# ESP32_radio_rev1_0.net
KiCad netlist of a schematic drawn in EAGLE
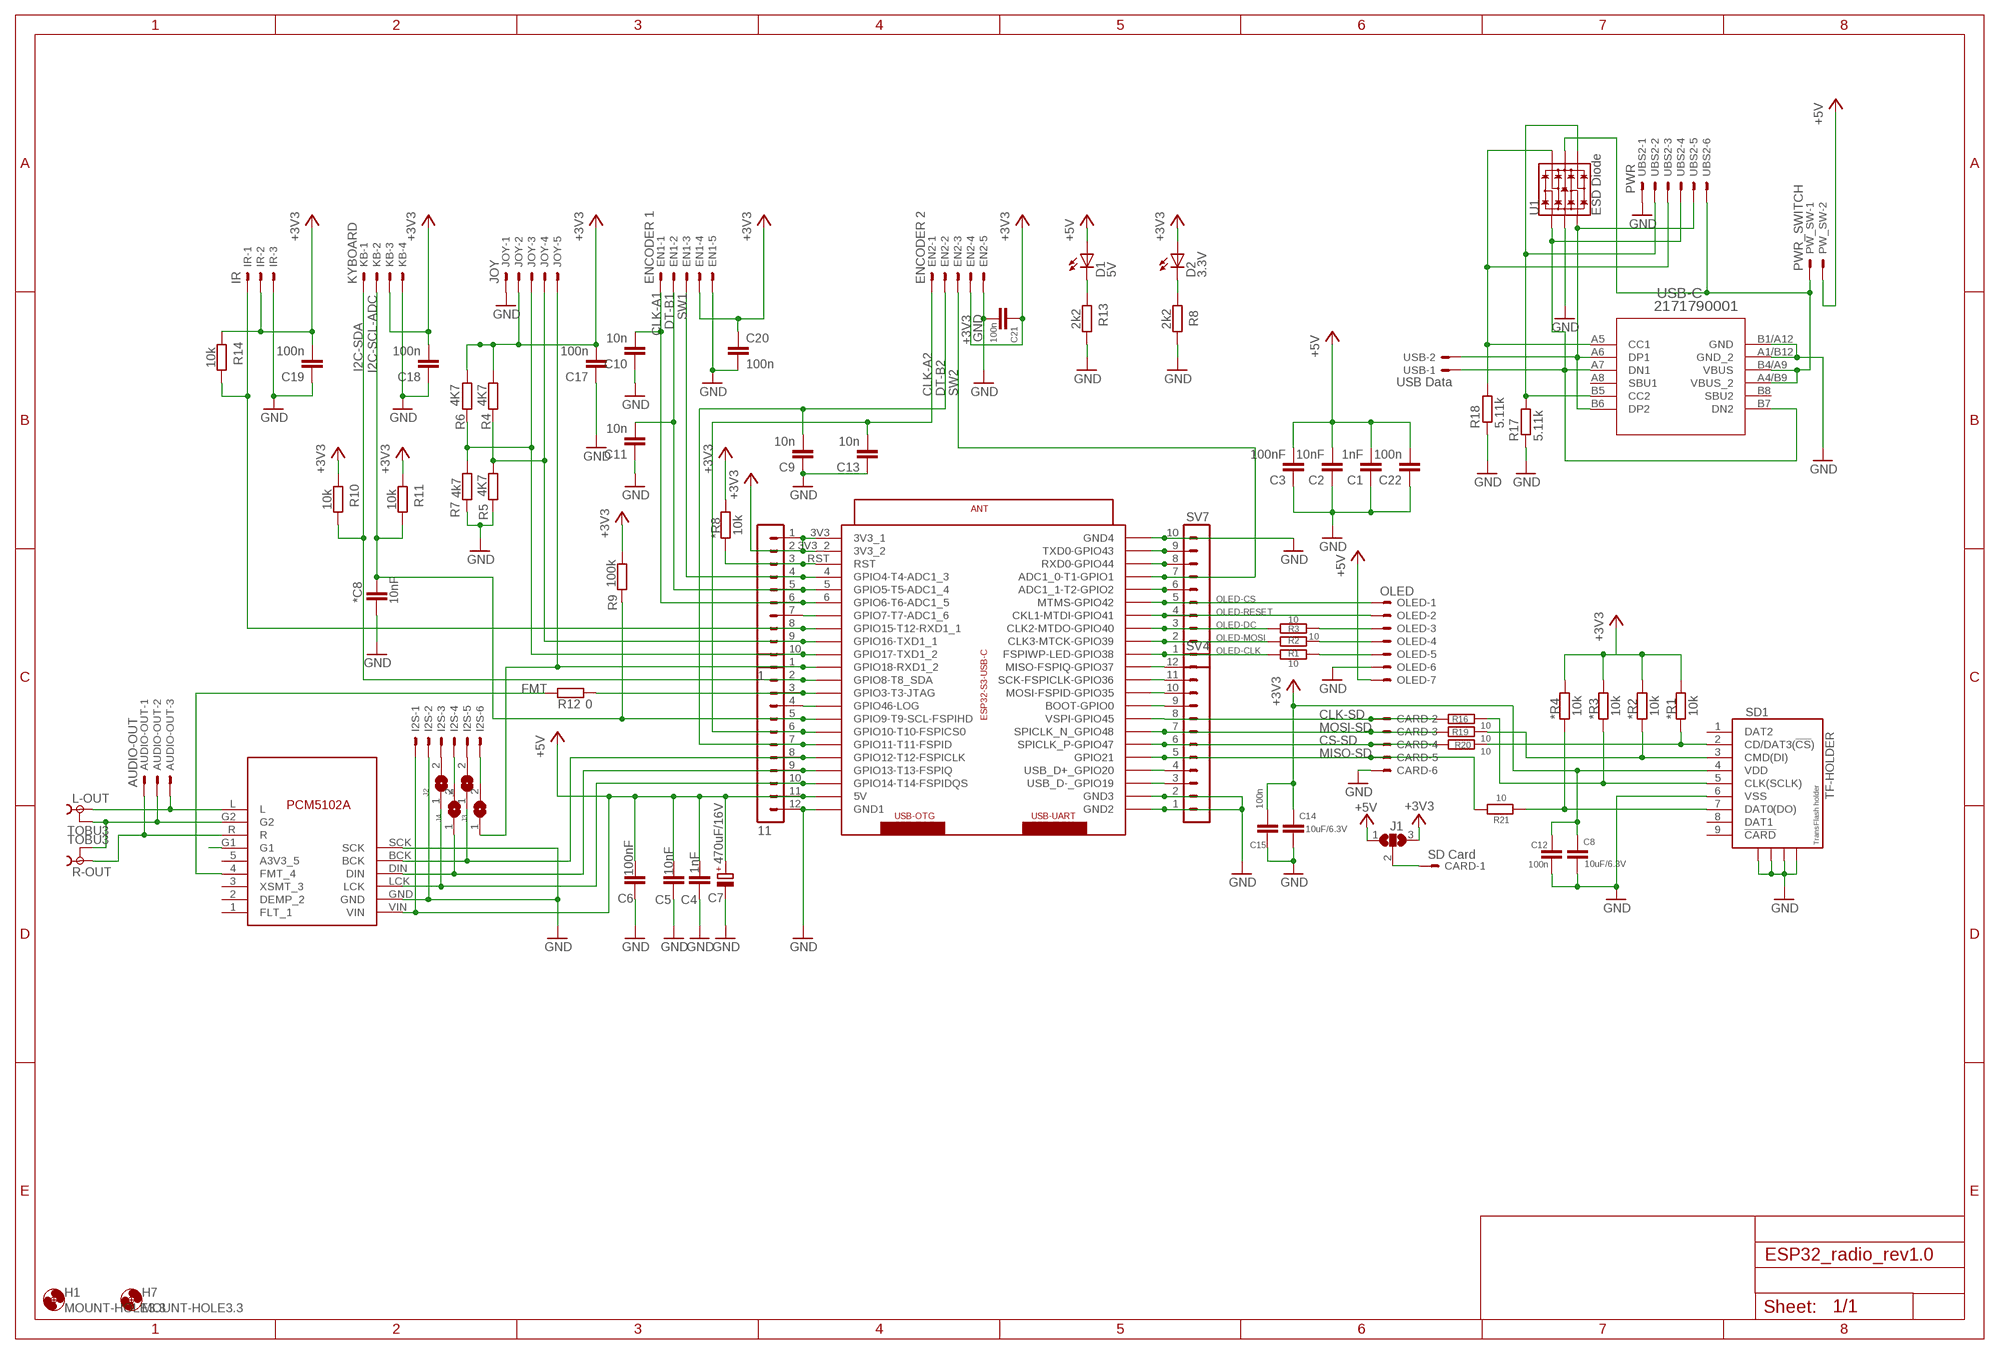
[diagram p0: schematic, sheet 1]

(export (version "E")
  (design (tool "Eeschema 10.0.6"))
  (components
    (comp (ref "*C8")
      (value "10nF")
      (footprint "eagle-import:C0603")
      (libsource (lib "eagle-import") (part "C-EUC0603"))
    )
    (comp (ref "*R1")
      (value "10k")
      (footprint "eagle-import:R0603")
      (libsource (lib "eagle-import") (part "R-EU_R0603"))
    )
    (comp (ref "*R2")
      (value "10k")
      (footprint "eagle-import:R0603")
      (libsource (lib "eagle-import") (part "R-EU_R0603"))
    )
    (comp (ref "*R3")
      (value "10k")
      (footprint "eagle-import:R0603")
      (libsource (lib "eagle-import") (part "R-EU_R0603"))
    )
    (comp (ref "*R4")
      (value "10k")
      (footprint "eagle-import:R0603")
      (libsource (lib "eagle-import") (part "R-EU_R0603"))
    )
    (comp (ref "*R8")
      (value "10k")
      (footprint "eagle-import:R0603")
      (libsource (lib "eagle-import") (part "R-EU_R0603"))
    )
    (comp (ref "1")
      (value "MA10-1")
      (footprint "eagle-import:MA10-1")
      (libsource (lib "eagle-import") (part "MA10-1"))
    )
    (comp (ref "11")
      (value "MA12-1")
      (footprint "eagle-import:MA12-1")
      (libsource (lib "eagle-import") (part "MA12-1"))
    )
    (comp (ref "AUDIO-OUT")
      (value "AUDIO-OUT")
      (footprint "eagle-import:JST-XH-03-PACKAGE-LONG-PAD")
      (libsource (lib "eagle-import") (part "JST-XH-03-PIN-LONG-PAD"))
    )
    (comp (ref "C1")
      (value "1nF")
      (footprint "eagle-import:C0603")
      (libsource (lib "eagle-import") (part "C-EUC0603"))
    )
    (comp (ref "C2")
      (value "10nF")
      (footprint "eagle-import:C0603")
      (libsource (lib "eagle-import") (part "C-EUC0603"))
    )
    (comp (ref "C3")
      (value "100nF")
      (footprint "eagle-import:C0603")
      (libsource (lib "eagle-import") (part "C-EUC0603"))
    )
    (comp (ref "C4")
      (value "1nF")
      (footprint "eagle-import:C0603")
      (libsource (lib "eagle-import") (part "C-EUC0603"))
    )
    (comp (ref "C5")
      (value "10nF")
      (footprint "eagle-import:C0603")
      (libsource (lib "eagle-import") (part "C-EUC0603"))
    )
    (comp (ref "C6")
      (value "100nF")
      (footprint "eagle-import:C0603")
      (libsource (lib "eagle-import") (part "C-EUC0603"))
    )
    (comp (ref "C7")
      (value "470uF/16V")
      (footprint "eagle-import:150CLZ-1010")
      (libsource (lib "eagle-import") (part "CPOL-EU150CLZ-1010"))
    )
    (comp (ref "C8")
      (value "10uF/6.3V")
      (footprint "eagle-import:C1210")
      (libsource (lib "eagle-import") (part "C-EUC1210"))
    )
    (comp (ref "C9")
      (value "10n")
      (footprint "eagle-import:C0603")
      (libsource (lib "eagle-import") (part "C-EUC0603"))
    )
    (comp (ref "C10")
      (value "10n")
      (footprint "eagle-import:C0603")
      (libsource (lib "eagle-import") (part "C-EUC0603"))
    )
    (comp (ref "C11")
      (value "10n")
      (footprint "eagle-import:C0603")
      (libsource (lib "eagle-import") (part "C-EUC0603"))
    )
    (comp (ref "C12")
      (value "100n")
      (footprint "eagle-import:C0603")
      (libsource (lib "eagle-import") (part "C-EUC0603"))
    )
    (comp (ref "C13")
      (value "10n")
      (footprint "eagle-import:C0603")
      (libsource (lib "eagle-import") (part "C-EUC0603"))
    )
    (comp (ref "C14")
      (value "10uF/6.3V")
      (footprint "eagle-import:C1210")
      (libsource (lib "eagle-import") (part "C-EUC1210"))
    )
    (comp (ref "C15")
      (value "100n")
      (footprint "eagle-import:C0603")
      (libsource (lib "eagle-import") (part "C-EUC0603"))
    )
    (comp (ref "C17")
      (value "100n")
      (footprint "eagle-import:C0603")
      (libsource (lib "eagle-import") (part "C-EUC0603"))
    )
    (comp (ref "C18")
      (value "100n")
      (footprint "eagle-import:C0603")
      (libsource (lib "eagle-import") (part "C-EUC0603"))
    )
    (comp (ref "C19")
      (value "100n")
      (footprint "eagle-import:C0603")
      (libsource (lib "eagle-import") (part "C-EUC0603"))
    )
    (comp (ref "C20")
      (value "100n")
      (footprint "eagle-import:C0603")
      (libsource (lib "eagle-import") (part "C-EUC0603"))
    )
    (comp (ref "C21")
      (value "100n")
      (footprint "eagle-import:C0603")
      (libsource (lib "eagle-import") (part "C-EUC0603"))
    )
    (comp (ref "C22")
      (value "100n")
      (footprint "eagle-import:C0603")
      (libsource (lib "eagle-import") (part "C-EUC0603"))
    )
    (comp (ref "CARD")
      (value "SD Card")
      (footprint "eagle-import:JST-XH-06-PACKAGE-LONG-PAD")
      (libsource (lib "eagle-import") (part "JST-XH-06-PIN-LONG-PAD"))
    )
    (comp (ref "D1")
      (value "5V")
      (footprint "eagle-import:CHIP-LED0805")
      (libsource (lib "eagle-import") (part "LEDCHIP-LED0805"))
    )
    (comp (ref "D2")
      (value "3.3V")
      (footprint "eagle-import:CHIP-LED0805")
      (libsource (lib "eagle-import") (part "LEDCHIP-LED0805"))
    )
    (comp (ref "EN1")
      (value "ENCODER 1")
      (footprint "eagle-import:JST-XH-05-PACKAGE-LONG-PAD")
      (libsource (lib "eagle-import") (part "JST-XH-05-PIN-LONG-PAD"))
    )
    (comp (ref "EN2")
      (value "ENCODER 2")
      (footprint "eagle-import:JST-XH-05-PACKAGE-LONG-PAD")
      (libsource (lib "eagle-import") (part "JST-XH-05-PIN-LONG-PAD"))
    )
    (comp (ref "H1")
      (value "MOUNT-HOLE3.3")
      (footprint "eagle-import:3,3")
      (libsource (lib "eagle-import") (part "MOUNT-HOLE3.3"))
    )
    (comp (ref "H7")
      (value "MOUNT-HOLE3.3")
      (footprint "eagle-import:3,3")
      (libsource (lib "eagle-import") (part "MOUNT-HOLE3.3"))
    )
    (comp (ref "I2S")
      (value "JST-XH-06-PIN-LONG-PAD")
      (footprint "eagle-import:JST-XH-06-PACKAGE-LONG-PAD")
      (libsource (lib "eagle-import") (part "JST-XH-06-PIN-LONG-PAD"))
    )
    (comp (ref "IR")
      (value "IR")
      (footprint "eagle-import:JST-XH-03-PACKAGE-LONG-PAD")
      (libsource (lib "eagle-import") (part "JST-XH-03-PIN-LONG-PAD"))
    )
    (comp (ref "J1")
      (value "SJ2W")
      (footprint "eagle-import:SJ_2")
      (libsource (lib "eagle-import") (part "SJ2W"))
    )
    (comp (ref "J2") (value "SJ") (footprint "eagle-import:SJ") (libsource (lib "eagle-import") (part "SJ")))
    (comp (ref "J3") (value "SJ") (footprint "eagle-import:SJ") (libsource (lib "eagle-import") (part "SJ")))
    (comp (ref "J4") (value "SJ") (footprint "eagle-import:SJ") (libsource (lib "eagle-import") (part "SJ")))
    (comp (ref "J5") (value "SJ") (footprint "eagle-import:SJ") (libsource (lib "eagle-import") (part "SJ")))
    (comp (ref "JOY")
      (value "JOY")
      (footprint "eagle-import:JST-XH-05-PACKAGE-LONG-PAD")
      (libsource (lib "eagle-import") (part "JST-XH-05-PIN-LONG-PAD"))
    )
    (comp (ref "KB")
      (value "KYBOARD")
      (footprint "eagle-import:JST-XH-04-PACKAGE-LONG-PAD")
      (libsource (lib "eagle-import") (part "JST-XH-04-PIN-LONG-PAD"))
    )
    (comp (ref "L-OUT")
      (value "TOBU3")
      (footprint "eagle-import:TOBU3")
      (fields (field (name "MF") "FARNELL") (field (name "MPN") "TOBU 3"))
      (libsource (lib "eagle-import") (part "TOBU3"))
    )
    (comp (ref "M2")
      (value "I2S_PCM_51XX_SOUNDCARD")
      (footprint "eagle-import:I2S_PCM_5100_SOUNDCARD")
      (libsource (lib "eagle-import") (part "I2S_PCM_51XX_SOUNDCARD"))
    )
    (comp (ref "OLED")
      (value "OLED")
      (footprint "eagle-import:JST-XH-07-PACKAGE-LONG-PAD")
      (libsource (lib "eagle-import") (part "JST-XH-07-PIN-LONG-PAD"))
    )
    (comp (ref "PW_SW")
      (value "PWR_SWITCH")
      (footprint "eagle-import:JST-XH-02-PACKAGE-LONG-PAD")
      (libsource (lib "eagle-import") (part "JST-XH-02-PIN-LONG-PAD"))
    )
    (comp (ref "R-OUT")
      (value "TOBU3")
      (footprint "eagle-import:TOBU3")
      (fields (field (name "MF") "FARNELL") (field (name "MPN") "TOBU 3"))
      (libsource (lib "eagle-import") (part "TOBU3"))
    )
    (comp (ref "R1")
      (value "10")
      (footprint "eagle-import:R0603")
      (libsource (lib "eagle-import") (part "R-EU_R0603"))
    )
    (comp (ref "R2")
      (value "10")
      (footprint "eagle-import:R0603")
      (libsource (lib "eagle-import") (part "R-EU_R0603"))
    )
    (comp (ref "R3")
      (value "10")
      (footprint "eagle-import:R0603")
      (libsource (lib "eagle-import") (part "R-EU_R0603"))
    )
    (comp (ref "R4")
      (value "4K7")
      (footprint "eagle-import:R0603")
      (libsource (lib "eagle-import") (part "R-EU_R0603"))
    )
    (comp (ref "R5")
      (value "4K7")
      (footprint "eagle-import:R0603")
      (libsource (lib "eagle-import") (part "R-EU_R0603"))
    )
    (comp (ref "R6")
      (value "4K7")
      (footprint "eagle-import:R0603")
      (libsource (lib "eagle-import") (part "R-EU_R0603"))
    )
    (comp (ref "R7")
      (value "4k7")
      (footprint "eagle-import:R0603")
      (libsource (lib "eagle-import") (part "R-EU_R0603"))
    )
    (comp (ref "R8")
      (value "2k2")
      (footprint "eagle-import:R0603")
      (libsource (lib "eagle-import") (part "R-EU_R0603"))
    )
    (comp (ref "R9")
      (value "100k")
      (footprint "eagle-import:R0603")
      (libsource (lib "eagle-import") (part "R-EU_R0603"))
    )
    (comp (ref "R10")
      (value "10k")
      (footprint "eagle-import:R0603")
      (libsource (lib "eagle-import") (part "R-EU_R0603"))
    )
    (comp (ref "R11")
      (value "10k")
      (footprint "eagle-import:R0603")
      (libsource (lib "eagle-import") (part "R-EU_R0603"))
    )
    (comp (ref "R12")
      (value "0")
      (footprint "eagle-import:R0603")
      (libsource (lib "eagle-import") (part "R-EU_R0603"))
    )
    (comp (ref "R13")
      (value "2k2")
      (footprint "eagle-import:R0603")
      (libsource (lib "eagle-import") (part "R-EU_R0603"))
    )
    (comp (ref "R14")
      (value "10k")
      (footprint "eagle-import:R0603")
      (libsource (lib "eagle-import") (part "R-EU_R0603"))
    )
    (comp (ref "R16")
      (value "10")
      (footprint "eagle-import:R0603")
      (libsource (lib "eagle-import") (part "R-EU_R0603"))
    )
    (comp (ref "R17")
      (value "5.11k")
      (footprint "eagle-import:R0603")
      (libsource (lib "eagle-import") (part "R-EU_R0603"))
    )
    (comp (ref "R18")
      (value "5.11k")
      (footprint "eagle-import:R0603")
      (libsource (lib "eagle-import") (part "R-EU_R0603"))
    )
    (comp (ref "R19")
      (value "10")
      (footprint "eagle-import:R0603")
      (libsource (lib "eagle-import") (part "R-EU_R0603"))
    )
    (comp (ref "R20")
      (value "10")
      (footprint "eagle-import:R0603")
      (libsource (lib "eagle-import") (part "R-EU_R0603"))
    )
    (comp (ref "R21")
      (value "10")
      (footprint "eagle-import:R0603")
      (libsource (lib "eagle-import") (part "R-EU_R0603"))
    )
    (comp (ref "SD1")
      (value "TF-HOLDER")
      (footprint "eagle-import:TF-PULL")
      (libsource (lib "eagle-import") (part "TF-HOLDER"))
    )
    (comp (ref "SV4")
      (value "MA12-1")
      (footprint "eagle-import:MA12-1")
      (libsource (lib "eagle-import") (part "MA12-1"))
    )
    (comp (ref "SV7")
      (value "MA10-1")
      (footprint "eagle-import:MA10-1")
      (libsource (lib "eagle-import") (part "con-lstb_MA10-1"))
    )
    (comp (ref "U$1")
      (value "ESP32-S3-USBC")
      (footprint "eagle-import:ESP32-S3-USBC")
      (libsource (lib "eagle-import") (part "ESP32-S3-USBC"))
    )
    (comp (ref "U1")
      (value "ESD Diode")
      (footprint "eagle-import:SOT-23-6")
      (libsource (lib "eagle-import") (part "TVS_DIODE_ARRAY_DT1042-04SO-7"))
    )
    (comp (ref "UBS2")
      (value "PWR")
      (footprint "eagle-import:JST-XH-06-PACKAGE-LONG-PAD")
      (libsource (lib "eagle-import") (part "JST-XH-06-PIN-LONG-PAD"))
    )
    (comp (ref "USB")
      (value "USB Data")
      (footprint "eagle-import:JST-XH-02-PACKAGE-LONG-PAD")
      (libsource (lib "eagle-import") (part "JST-XH-02-PIN-LONG-PAD"))
    )
    (comp (ref "USB-C")
      (value "2171790001")
      (footprint "eagle-import:2171790001_MOL")
      (fields
        (field (name "MANUFACTURER_PART_NUMBER") "USB4105-GF-A-120")
        (field (name "COPYRIGHT") "Copyright (C) 2025 GRo")
      )
      (libsource (lib "eagle-import") (part "2171790001"))
    )
  )
  (nets
    (net (code "1") (name "+3V3") (class "Default")
      (node (ref "*R1") (pin "1") (pinfunction "1_1") (pintype "passive"))
      (node (ref "*R2") (pin "1") (pinfunction "1_1") (pintype "passive"))
      (node (ref "*R3") (pin "1") (pinfunction "1_1") (pintype "passive"))
      (node (ref "*R4") (pin "1") (pinfunction "1_1") (pintype "passive"))
      (node (ref "*R8") (pin "1") (pinfunction "1_1") (pintype "passive"))
      (node (ref "1") (pin "1") (pinfunction "1_1") (pintype "passive"))
      (node (ref "1") (pin "2") (pinfunction "2_2") (pintype "passive"))
      (node (ref "C12") (pin "2") (pinfunction "2_2") (pintype "passive"))
      (node (ref "C14") (pin "1") (pinfunction "1_1") (pintype "passive"))
      (node (ref "C15") (pin "2") (pinfunction "2_2") (pintype "passive"))
      (node (ref "C17") (pin "2") (pinfunction "2_2") (pintype "passive"))
      (node (ref "C18") (pin "2") (pinfunction "2_2") (pintype "passive"))
      (node (ref "C19") (pin "2") (pinfunction "2_2") (pintype "passive"))
      (node (ref "C20") (pin "1") (pinfunction "1_1") (pintype "passive"))
      (node (ref "C21") (pin "1") (pinfunction "1_1") (pintype "passive"))
      (node (ref "C8") (pin "1") (pinfunction "1_1") (pintype "passive"))
      (node (ref "D2") (pin "A") (pinfunction "A_A") (pintype "passive"))
      (node (ref "EN1") (pin "4") (pinfunction "S_4") (pintype "passive"))
      (node (ref "EN2") (pin "4") (pinfunction "S_4") (pintype "passive"))
      (node (ref "IR") (pin "2") (pinfunction "S_2") (pintype "passive"))
      (node (ref "J1") (pin "3") (pinfunction "3_3") (pintype "passive"))
      (node (ref "JOY") (pin "2") (pinfunction "S_2") (pintype "passive"))
      (node (ref "KB") (pin "3") (pinfunction "S_3") (pintype "passive"))
      (node (ref "R10") (pin "2") (pinfunction "2_2") (pintype "passive"))
      (node (ref "R11") (pin "2") (pinfunction "2_2") (pintype "passive"))
      (node (ref "R14") (pin "2") (pinfunction "2_2") (pintype "passive"))
      (node (ref "R4") (pin "2") (pinfunction "2_2") (pintype "passive"))
      (node (ref "R6") (pin "2") (pinfunction "2_2") (pintype "passive"))
      (node (ref "R9") (pin "2") (pinfunction "2_2") (pintype "passive"))
      (node (ref "SD1") (pin "4") (pinfunction "VDD_4") (pintype "power_in"))
      (node (ref "U$1") (pin "3V3") (pinfunction "3V3_1_3V3") (pintype "power_in"))
      (node (ref "U$1") (pin "3V3_2") (pinfunction "3V3_2_3V3_2") (pintype "power_in"))
    )
    (net (code "2") (name "+5V") (class "Default")
      (node (ref "11") (pin "11") (pinfunction "11_11") (pintype "passive"))
      (node (ref "C1") (pin "2") (pinfunction "2_2") (pintype "passive"))
      (node (ref "C2") (pin "2") (pinfunction "2_2") (pintype "passive"))
      (node (ref "C22") (pin "2") (pinfunction "2_2") (pintype "passive"))
      (node (ref "C3") (pin "2") (pinfunction "2_2") (pintype "passive"))
      (node (ref "C4") (pin "2") (pinfunction "2_2") (pintype "passive"))
      (node (ref "C5") (pin "2") (pinfunction "2_2") (pintype "passive"))
      (node (ref "C6") (pin "2") (pinfunction "2_2") (pintype "passive"))
      (node (ref "C7") (pin "+") (pinfunction "+_+") (pintype "passive"))
      (node (ref "D1") (pin "A") (pinfunction "A_A") (pintype "passive"))
      (node (ref "I2S") (pin "1") (pinfunction "S_1") (pintype "passive"))
      (node (ref "J1") (pin "1") (pinfunction "1_1") (pintype "passive"))
      (node (ref "M2") (pin "VIN") (pinfunction "VIN_VIN") (pintype "bidirectional"))
      (node (ref "OLED") (pin "7") (pinfunction "S_7") (pintype "passive"))
      (node (ref "PW_SW") (pin "2") (pinfunction "S_2") (pintype "passive"))
      (node (ref "U$1") (pin "5V") (pinfunction "5V_5V") (pintype "power_in"))
    )
    (net (code "3") (name "/CLK-A1") (class "Default")
      (node (ref "1") (pin "6") (pinfunction "6_6") (pintype "passive"))
      (node (ref "C10") (pin "2") (pinfunction "2_2") (pintype "passive"))
      (node (ref "EN1") (pin "1") (pinfunction "S_1") (pintype "passive"))
      (node (ref "U$1") (pin "6") (pinfunction "GPIO6-T6-ADC1_5_6") (pintype "bidirectional"))
    )
    (net (code "4") (name "/CLK-A2") (class "Default")
      (node (ref "11") (pin "6") (pinfunction "6_6") (pintype "passive"))
      (node (ref "C13") (pin "2") (pinfunction "2_2") (pintype "passive"))
      (node (ref "EN2") (pin "1") (pinfunction "S_1") (pintype "passive"))
      (node (ref "U$1") (pin "10") (pinfunction "GPIO10-T10-FSPICS0_10") (pintype "bidirectional"))
    )
    (net (code "5") (name "/CLK-SD") (class "Default")
      (node (ref "CARD") (pin "2") (pinfunction "S_2") (pintype "passive"))
      (node (ref "R16") (pin "1") (pinfunction "1_1") (pintype "passive"))
      (node (ref "SV4") (pin "8") (pinfunction "8_8") (pintype "passive"))
      (node (ref "U$1") (pin "45") (pinfunction "VSPI-GPIO45_45") (pintype "bidirectional"))
    )
    (net (code "6") (name "/CS-SD") (class "Default")
      (node (ref "CARD") (pin "4") (pinfunction "S_4") (pintype "passive"))
      (node (ref "R20") (pin "1") (pinfunction "1_1") (pintype "passive"))
      (node (ref "SV4") (pin "6") (pinfunction "6_6") (pintype "passive"))
      (node (ref "U$1") (pin "47") (pinfunction "SPICLK_P-GPIO47_47") (pintype "bidirectional"))
    )
    (net (code "7") (name "/DT-B1") (class "Default")
      (node (ref "1") (pin "5") (pinfunction "5_5") (pintype "passive"))
      (node (ref "C11") (pin "2") (pinfunction "2_2") (pintype "passive"))
      (node (ref "EN1") (pin "2") (pinfunction "S_2") (pintype "passive"))
      (node (ref "U$1") (pin "5") (pinfunction "GPIO5-T5-ADC1_4_5") (pintype "bidirectional"))
    )
    (net (code "8") (name "/DT-B2") (class "Default")
      (node (ref "11") (pin "7") (pinfunction "7_7") (pintype "passive"))
      (node (ref "C9") (pin "2") (pinfunction "2_2") (pintype "passive"))
      (node (ref "EN2") (pin "2") (pinfunction "S_2") (pintype "passive"))
      (node (ref "U$1") (pin "11") (pinfunction "GPIO11-T11-FSPID_11") (pintype "bidirectional"))
    )
    (net (code "9") (name "/FMT") (class "Default")
      (node (ref "M2") (pin "4") (pinfunction "FMT_4_4") (pintype "bidirectional"))
      (node (ref "R12") (pin "2") (pinfunction "2_2") (pintype "passive"))
    )
    (net (code "10") (name "/I2C-SCL-ADC") (class "Default")
      (node (ref "*C8") (pin "1") (pinfunction "1_1") (pintype "passive"))
      (node (ref "11") (pin "5") (pinfunction "5_5") (pintype "passive"))
      (node (ref "KB") (pin "2") (pinfunction "S_2") (pintype "passive"))
      (node (ref "R11") (pin "1") (pinfunction "1_1") (pintype "passive"))
      (node (ref "R9") (pin "1") (pinfunction "1_1") (pintype "passive"))
      (node (ref "U$1") (pin "9") (pinfunction "GPIO9-T9-SCL-FSPIHD_9") (pintype "bidirectional"))
    )
    (net (code "11") (name "/I2C-SDA") (class "Default")
      (node (ref "11") (pin "2") (pinfunction "2_2") (pintype "passive"))
      (node (ref "KB") (pin "1") (pinfunction "S_1") (pintype "passive"))
      (node (ref "R10") (pin "1") (pinfunction "1_1") (pintype "passive"))
      (node (ref "U$1") (pin "8") (pinfunction "GPIO8-T8_SDA_8") (pintype "bidirectional"))
    )
    (net (code "12") (name "/MISO-SD") (class "Default")
      (node (ref "CARD") (pin "5") (pinfunction "S_5") (pintype "passive"))
      (node (ref "R21") (pin "1") (pinfunction "1_1") (pintype "passive"))
      (node (ref "SV4") (pin "5") (pinfunction "5_5") (pintype "passive"))
      (node (ref "U$1") (pin "21") (pinfunction "GPIO21_21") (pintype "bidirectional"))
    )
    (net (code "13") (name "/MOSI-SD") (class "Default")
      (node (ref "CARD") (pin "3") (pinfunction "S_3") (pintype "passive"))
      (node (ref "R19") (pin "1") (pinfunction "1_1") (pintype "passive"))
      (node (ref "SV4") (pin "7") (pinfunction "7_7") (pintype "passive"))
      (node (ref "U$1") (pin "48") (pinfunction "SPICLK_N_GPIO48_48") (pintype "bidirectional"))
    )
    (net (code "14") (name "/OLED-CLK") (class "Default")
      (node (ref "R1") (pin "1") (pinfunction "1_1") (pintype "passive"))
      (node (ref "SV7") (pin "1") (pinfunction "1_1") (pintype "passive"))
      (node (ref "U$1") (pin "38") (pinfunction "FSPIWP-LED-GPIO38_38") (pintype "bidirectional"))
    )
    (net (code "15") (name "/OLED-CS") (class "Default")
      (node (ref "OLED") (pin "1") (pinfunction "S_1") (pintype "passive"))
      (node (ref "SV7") (pin "5") (pinfunction "5_5") (pintype "passive"))
      (node (ref "U$1") (pin "42") (pinfunction "MTMS-GPIO42_42") (pintype "bidirectional"))
    )
    (net (code "16") (name "/OLED-DC") (class "Default")
      (node (ref "R3") (pin "1") (pinfunction "1_1") (pintype "passive"))
      (node (ref "SV7") (pin "3") (pinfunction "3_3") (pintype "passive"))
      (node (ref "U$1") (pin "40") (pinfunction "CLK2-MTDO-GPIO40_40") (pintype "bidirectional"))
    )
    (net (code "17") (name "/OLED-MOSI") (class "Default")
      (node (ref "R2") (pin "1") (pinfunction "1_1") (pintype "passive"))
      (node (ref "SV7") (pin "2") (pinfunction "2_2") (pintype "passive"))
      (node (ref "U$1") (pin "39") (pinfunction "CLK3-MTCK-GPIO39_39") (pintype "bidirectional"))
    )
    (net (code "18") (name "/OLED-RESET") (class "Default")
      (node (ref "OLED") (pin "2") (pinfunction "S_2") (pintype "passive"))
      (node (ref "SV7") (pin "4") (pinfunction "4_4") (pintype "passive"))
      (node (ref "U$1") (pin "41") (pinfunction "CKL1-MTDI-GPIO41_41") (pintype "bidirectional"))
    )
    (net (code "19") (name "/SW1") (class "Default")
      (node (ref "1") (pin "4") (pinfunction "4_4") (pintype "passive"))
      (node (ref "EN1") (pin "3") (pinfunction "S_3") (pintype "passive"))
      (node (ref "U$1") (pin "4") (pinfunction "GPIO4-T4-ADC1_3_4") (pintype "bidirectional"))
    )
    (net (code "20") (name "/SW2") (class "Default")
      (node (ref "EN2") (pin "3") (pinfunction "S_3") (pintype "passive"))
      (node (ref "SV7") (pin "7") (pinfunction "7_7") (pintype "passive"))
      (node (ref "U$1") (pin "1") (pinfunction "ADC1_0-T1-GPIO1_1") (pintype "bidirectional"))
    )
    (net (code "21") (name "GND") (class "Default")
      (node (ref "*C8") (pin "2") (pinfunction "2_2") (pintype "passive"))
      (node (ref "11") (pin "12") (pinfunction "12_12") (pintype "passive"))
      (node (ref "C1") (pin "1") (pinfunction "1_1") (pintype "passive"))
      (node (ref "C10") (pin "1") (pinfunction "1_1") (pintype "passive"))
      (node (ref "C11") (pin "1") (pinfunction "1_1") (pintype "passive"))
      (node (ref "C12") (pin "1") (pinfunction "1_1") (pintype "passive"))
      (node (ref "C13") (pin "1") (pinfunction "1_1") (pintype "passive"))
      (node (ref "C14") (pin "2") (pinfunction "2_2") (pintype "passive"))
      (node (ref "C15") (pin "1") (pinfunction "1_1") (pintype "passive"))
      (node (ref "C17") (pin "1") (pinfunction "1_1") (pintype "passive"))
      (node (ref "C18") (pin "1") (pinfunction "1_1") (pintype "passive"))
      (node (ref "C19") (pin "1") (pinfunction "1_1") (pintype "passive"))
      (node (ref "C2") (pin "1") (pinfunction "1_1") (pintype "passive"))
      (node (ref "C20") (pin "2") (pinfunction "2_2") (pintype "passive"))
      (node (ref "C21") (pin "2") (pinfunction "2_2") (pintype "passive"))
      (node (ref "C22") (pin "1") (pinfunction "1_1") (pintype "passive"))
      (node (ref "C3") (pin "1") (pinfunction "1_1") (pintype "passive"))
      (node (ref "C4") (pin "1") (pinfunction "1_1") (pintype "passive"))
      (node (ref "C5") (pin "1") (pinfunction "1_1") (pintype "passive"))
      (node (ref "C6") (pin "1") (pinfunction "1_1") (pintype "passive"))
      (node (ref "C7") (pin "-") (pinfunction "-_-") (pintype "passive"))
      (node (ref "C8") (pin "2") (pinfunction "2_2") (pintype "passive"))
      (node (ref "C9") (pin "1") (pinfunction "1_1") (pintype "passive"))
      (node (ref "CARD") (pin "6") (pinfunction "S_6") (pintype "passive"))
      (node (ref "EN1") (pin "5") (pinfunction "S_5") (pintype "passive"))
      (node (ref "EN2") (pin "5") (pinfunction "S_5") (pintype "passive"))
      (node (ref "I2S") (pin "2") (pinfunction "S_2") (pintype "passive"))
      (node (ref "IR") (pin "3") (pinfunction "S_3") (pintype "passive"))
      (node (ref "JOY") (pin "1") (pinfunction "S_1") (pintype "passive"))
      (node (ref "KB") (pin "4") (pinfunction "S_4") (pintype "passive"))
      (node (ref "M2") (pin "GND") (pinfunction "GND_GND") (pintype "bidirectional"))
      (node (ref "M2") (pin "SCK") (pinfunction "SCK_SCK") (pintype "bidirectional"))
      (node (ref "OLED") (pin "6") (pinfunction "S_6") (pintype "passive"))
      (node (ref "R13") (pin "1") (pinfunction "1_1") (pintype "passive"))
      (node (ref "R17") (pin "1") (pinfunction "1_1") (pintype "passive"))
      (node (ref "R18") (pin "1") (pinfunction "1_1") (pintype "passive"))
      (node (ref "R5") (pin "1") (pinfunction "1_1") (pintype "passive"))
      (node (ref "R7") (pin "1") (pinfunction "1_1") (pintype "passive"))
      (node (ref "R8") (pin "1") (pinfunction "1_1") (pintype "passive"))
      (node (ref "SD1") (pin "6") (pinfunction "VSS_6") (pintype "power_in"))
      (node (ref "SD1") (pin "S1") (pinfunction "S1_S1") (pintype "passive"))
      (node (ref "SD1") (pin "S2") (pinfunction "S2_S2") (pintype "passive"))
      (node (ref "SD1") (pin "S3") (pinfunction "S3_S3") (pintype "passive"))
      (node (ref "SD1") (pin "S4") (pinfunction "S4_S4") (pintype "passive"))
      (node (ref "SV4") (pin "1") (pinfunction "1_1") (pintype "passive"))
      (node (ref "SV4") (pin "2") (pinfunction "2_2") (pintype "passive"))
      (node (ref "SV7") (pin "10") (pinfunction "10_10") (pintype "passive"))
      (node (ref "U$1") (pin "GND1") (pinfunction "GND1_GND1") (pintype "power_in"))
      (node (ref "U$1") (pin "GND2") (pinfunction "GND2_GND2") (pintype "power_in"))
      (node (ref "U$1") (pin "GND3") (pinfunction "GND3_GND3") (pintype "power_in"))
      (node (ref "U$1") (pin "GND4") (pinfunction "GND4_GND4") (pintype "power_in"))
      (node (ref "U1") (pin "2") (pinfunction "VSS_2") (pintype "bidirectional"))
      (node (ref "UBS2") (pin "1") (pinfunction "S_1") (pintype "passive"))
      (node (ref "USB-C") (pin "A1/B12") (pinfunction "GND_2_A1/B12") (pintype "passive"))
      (node (ref "USB-C") (pin "B1/A12") (pinfunction "GND_B1/A12") (pintype "passive"))
    )
    (net (code "22") (name "Net-(*R8-Pad2)") (class "Default")
      (node (ref "*R8") (pin "2") (pinfunction "2_2") (pintype "passive"))
      (node (ref "1") (pin "3") (pinfunction "3_3") (pintype "passive"))
      (node (ref "U$1") (pin "RST") (pinfunction "RST_RST") (pintype "bidirectional"))
    )
    (net (code "23") (name "Net-(AUDIO-OUTA-S)") (class "Default")
      (node (ref "AUDIO-OUT") (pin "1") (pinfunction "S_1") (pintype "passive"))
      (node (ref "M2") (pin "R") (pinfunction "R_R") (pintype "bidirectional"))
      (node (ref "R-OUT") (pin "1") (pinfunction "1_1") (pintype "passive"))
    )
    (net (code "24") (name "Net-(AUDIO-OUTB-S)") (class "Default")
      (node (ref "AUDIO-OUT") (pin "2") (pinfunction "S_2") (pintype "passive"))
      (node (ref "L-OUT") (pin "2") (pinfunction "2_2") (pintype "passive"))
      (node (ref "L-OUT") (pin "2@1") (pinfunction "2_2@1") (pintype "passive"))
      (node (ref "L-OUT") (pin "2@2") (pinfunction "2_2@2") (pintype "passive"))
      (node (ref "M2") (pin "G2") (pinfunction "G2_G2") (pintype "bidirectional"))
      (node (ref "R-OUT") (pin "2") (pinfunction "2_2") (pintype "passive"))
      (node (ref "R-OUT") (pin "2@1") (pinfunction "2_2@1") (pintype "passive"))
      (node (ref "R-OUT") (pin "2@2") (pinfunction "2_2@2") (pintype "passive"))
    )
    (net (code "25") (name "Net-(AUDIO-OUTC-S)") (class "Default")
      (node (ref "AUDIO-OUT") (pin "3") (pinfunction "S_3") (pintype "passive"))
      (node (ref "L-OUT") (pin "1") (pinfunction "1_1") (pintype "passive"))
      (node (ref "M2") (pin "L") (pinfunction "L_L") (pintype "bidirectional"))
    )
    (net (code "26") (name "Net-(CARDA-S)") (class "Default")
      (node (ref "CARD") (pin "1") (pinfunction "S_1") (pintype "passive"))
      (node (ref "J1") (pin "2") (pinfunction "2_2") (pintype "passive"))
    )
    (net (code "27") (name "Net-(D1-PadC)") (class "Default")
      (node (ref "D1") (pin "C") (pinfunction "C_C") (pintype "passive"))
      (node (ref "R13") (pin "2") (pinfunction "2_2") (pintype "passive"))
    )
    (net (code "28") (name "Net-(D2-PadC)") (class "Default")
      (node (ref "D2") (pin "C") (pinfunction "C_C") (pintype "passive"))
      (node (ref "R8") (pin "2") (pinfunction "2_2") (pintype "passive"))
    )
    (net (code "29") (name "Net-(I2SC-S)") (class "Default")
      (node (ref "I2S") (pin "3") (pinfunction "S_3") (pintype "passive"))
      (node (ref "J2") (pin "2") (pinfunction "2_2") (pintype "passive"))
    )
    (net (code "30") (name "Net-(I2SD-S)") (class "Default")
      (node (ref "I2S") (pin "4") (pinfunction "S_4") (pintype "passive"))
      (node (ref "J4") (pin "2") (pinfunction "2_2") (pintype "passive"))
    )
    (net (code "31") (name "Net-(I2SE-S)") (class "Default")
      (node (ref "I2S") (pin "5") (pinfunction "S_5") (pintype "passive"))
      (node (ref "J5") (pin "2") (pinfunction "2_2") (pintype "passive"))
    )
    (net (code "32") (name "Net-(I2SF-S)") (class "Default")
      (node (ref "I2S") (pin "6") (pinfunction "S_6") (pintype "passive"))
      (node (ref "J3") (pin "2") (pinfunction "2_2") (pintype "passive"))
    )
    (net (code "33") (name "Net-(IRA-S)") (class "Default")
      (node (ref "1") (pin "8") (pinfunction "8_8") (pintype "passive"))
      (node (ref "IR") (pin "1") (pinfunction "S_1") (pintype "passive"))
      (node (ref "R14") (pin "1") (pinfunction "1_1") (pintype "passive"))
      (node (ref "U$1") (pin "15") (pinfunction "GPIO15-T12-RXD1_1_15") (pintype "bidirectional"))
    )
    (net (code "34") (name "Net-(JOYC-S)") (class "Default")
      (node (ref "1") (pin "10") (pinfunction "10_10") (pintype "passive"))
      (node (ref "JOY") (pin "3") (pinfunction "S_3") (pintype "passive"))
      (node (ref "R6") (pin "1") (pinfunction "1_1") (pintype "passive"))
      (node (ref "R7") (pin "2") (pinfunction "2_2") (pintype "passive"))
      (node (ref "U$1") (pin "17") (pinfunction "GPIO17-TXD1_2_17") (pintype "bidirectional"))
    )
    (net (code "35") (name "Net-(JOYD-S)") (class "Default")
      (node (ref "1") (pin "9") (pinfunction "9_9") (pintype "passive"))
      (node (ref "JOY") (pin "4") (pinfunction "S_4") (pintype "passive"))
      (node (ref "R4") (pin "1") (pinfunction "1_1") (pintype "passive"))
      (node (ref "R5") (pin "2") (pinfunction "2_2") (pintype "passive"))
      (node (ref "U$1") (pin "16") (pinfunction "GPIO16-TXD1_1_16") (pintype "bidirectional"))
    )
    (net (code "36") (name "Net-(JOYE-S)") (class "Default")
      (node (ref "11") (pin "1") (pinfunction "1_1") (pintype "passive"))
      (node (ref "J3") (pin "1") (pinfunction "1_1") (pintype "passive"))
      (node (ref "JOY") (pin "5") (pinfunction "S_5") (pintype "passive"))
      (node (ref "U$1") (pin "18") (pinfunction "GPIO18-RXD1_2_18") (pintype "bidirectional"))
    )
    (net (code "37") (name "Net-(OLEDC-S)") (class "Default")
      (node (ref "OLED") (pin "3") (pinfunction "S_3") (pintype "passive"))
      (node (ref "R3") (pin "2") (pinfunction "2_2") (pintype "passive"))
    )
    (net (code "38") (name "Net-(OLEDD-S)") (class "Default")
      (node (ref "OLED") (pin "4") (pinfunction "S_4") (pintype "passive"))
      (node (ref "R2") (pin "2") (pinfunction "2_2") (pintype "passive"))
    )
    (net (code "39") (name "Net-(OLEDE-S)") (class "Default")
      (node (ref "OLED") (pin "5") (pinfunction "S_5") (pintype "passive"))
      (node (ref "R1") (pin "2") (pinfunction "2_2") (pintype "passive"))
    )
    (net (code "40") (name "Net-(PW_SWA-S)") (class "Default")
      (node (ref "PW_SW") (pin "1") (pinfunction "S_1") (pintype "passive"))
      (node (ref "U1") (pin "5") (pinfunction "VCC_5") (pintype "bidirectional"))
      (node (ref "UBS2") (pin "6") (pinfunction "S_6") (pintype "passive"))
      (node (ref "USB-C") (pin "A4/B9") (pinfunction "VBUS_2_A4/B9") (pintype "power_in"))
      (node (ref "USB-C") (pin "B4/A9") (pinfunction "VBUS_B4/A9") (pintype "power_in"))
    )
    (net (code "41") (name "Net-(SD1-CD{slash}DAT3(~{CS}))") (class "Default")
      (node (ref "*R1") (pin "2") (pinfunction "2_2") (pintype "passive"))
      (node (ref "R20") (pin "2") (pinfunction "2_2") (pintype "passive"))
      (node (ref "SD1") (pin "2") (pinfunction "CD/DAT3(~{CS})_2") (pintype "bidirectional"))
    )
    (net (code "42") (name "Net-(SD1-CLK(SCLK))") (class "Default")
      (node (ref "*R3") (pin "2") (pinfunction "2_2") (pintype "passive"))
      (node (ref "R16") (pin "2") (pinfunction "2_2") (pintype "passive"))
      (node (ref "SD1") (pin "5") (pinfunction "CLK(SCLK)_5") (pintype "input"))
    )
    (net (code "43") (name "Net-(SD1-CMD(DI))") (class "Default")
      (node (ref "*R2") (pin "2") (pinfunction "2_2") (pintype "passive"))
      (node (ref "R19") (pin "2") (pinfunction "2_2") (pintype "passive"))
      (node (ref "SD1") (pin "3") (pinfunction "CMD(DI)_3") (pintype "bidirectional"))
    )
    (net (code "44") (name "Net-(SD1-DAT0(DO))") (class "Default")
      (node (ref "*R4") (pin "2") (pinfunction "2_2") (pintype "passive"))
      (node (ref "R21") (pin "2") (pinfunction "2_2") (pintype "passive"))
      (node (ref "SD1") (pin "7") (pinfunction "DAT0(DO)_7") (pintype "bidirectional"))
    )
    (net (code "45") (name "Net-(U$1-ADC1_1-T2-GPIO2)") (class "Default")
      (node (ref "SV7") (pin "6") (pinfunction "6_6") (pintype "passive"))
      (node (ref "U$1") (pin "2") (pinfunction "ADC1_1-T2-GPIO2_2") (pintype "bidirectional"))
    )
    (net (code "46") (name "Net-(U$1-BOOT-GPIO0)") (class "Default")
      (node (ref "SV4") (pin "9") (pinfunction "9_9") (pintype "passive"))
      (node (ref "U$1") (pin "0") (pinfunction "BOOT-GPIO0_0") (pintype "bidirectional"))
    )
    (net (code "47") (name "Net-(U$1-GPIO3-T3-JTAG)") (class "Default")
      (node (ref "11") (pin "3") (pinfunction "3_3") (pintype "passive"))
      (node (ref "R12") (pin "1") (pinfunction "1_1") (pintype "passive"))
      (node (ref "U$1") (pin "3") (pinfunction "GPIO3-T3-JTAG_3") (pintype "bidirectional"))
    )
    (net (code "48") (name "Net-(U$1-GPIO7-T7-ADC1_6)") (class "Default")
      (node (ref "1") (pin "7") (pinfunction "7_7") (pintype "passive"))
      (node (ref "U$1") (pin "7") (pinfunction "GPIO7-T7-ADC1_6_7") (pintype "bidirectional"))
    )
    (net (code "49") (name "Net-(U$1-GPIO12-T12-FSPICLK)") (class "Default")
      (node (ref "11") (pin "8") (pinfunction "8_8") (pintype "passive"))
      (node (ref "J5") (pin "1") (pinfunction "1_1") (pintype "passive"))
      (node (ref "M2") (pin "BCK") (pinfunction "BCK_BCK") (pintype "bidirectional"))
      (node (ref "U$1") (pin "12") (pinfunction "GPIO12-T12-FSPICLK_12") (pintype "bidirectional"))
    )
    (net (code "50") (name "Net-(U$1-GPIO13-T13-FSPIQ)") (class "Default")
      (node (ref "11") (pin "9") (pinfunction "9_9") (pintype "passive"))
      (node (ref "J4") (pin "1") (pinfunction "1_1") (pintype "passive"))
      (node (ref "M2") (pin "DIN") (pinfunction "DIN_DIN") (pintype "bidirectional"))
      (node (ref "U$1") (pin "13") (pinfunction "GPIO13-T13-FSPIQ_13") (pintype "bidirectional"))
    )
    (net (code "51") (name "Net-(U$1-GPIO14-T14-FSPIDQS)") (class "Default")
      (node (ref "11") (pin "10") (pinfunction "10_10") (pintype "passive"))
      (node (ref "J2") (pin "1") (pinfunction "1_1") (pintype "passive"))
      (node (ref "M2") (pin "LCK") (pinfunction "LCK_LCK") (pintype "bidirectional"))
      (node (ref "U$1") (pin "14") (pinfunction "GPIO14-T14-FSPIDQS_14") (pintype "bidirectional"))
    )
    (net (code "52") (name "Net-(U$1-GPIO46-LOG)") (class "Default")
      (node (ref "11") (pin "4") (pinfunction "4_4") (pintype "passive"))
      (node (ref "U$1") (pin "46") (pinfunction "GPIO46-LOG_46") (pintype "bidirectional"))
    )
    (net (code "53") (name "Net-(U$1-MISO-FSPIQ-GPIO37)") (class "Default")
      (node (ref "SV4") (pin "12") (pinfunction "12_12") (pintype "passive"))
      (node (ref "U$1") (pin "37") (pinfunction "MISO-FSPIQ-GPIO37_37") (pintype "bidirectional"))
    )
    (net (code "54") (name "Net-(U$1-MOSI-FSPID-GPIO35)") (class "Default")
      (node (ref "SV4") (pin "10") (pinfunction "10_10") (pintype "passive"))
      (node (ref "U$1") (pin "35") (pinfunction "MOSI-FSPID-GPIO35_35") (pintype "bidirectional"))
    )
    (net (code "55") (name "Net-(U$1-RXD0-GPIO44)") (class "Default")
      (node (ref "SV7") (pin "8") (pinfunction "8_8") (pintype "passive"))
      (node (ref "U$1") (pin "44") (pinfunction "RXD0-GPIO44_44") (pintype "bidirectional"))
    )
    (net (code "56") (name "Net-(U$1-SCK-FSPICLK-GPIO36)") (class "Default")
      (node (ref "SV4") (pin "11") (pinfunction "11_11") (pintype "passive"))
      (node (ref "U$1") (pin "36") (pinfunction "SCK-FSPICLK-GPIO36_36") (pintype "bidirectional"))
    )
    (net (code "57") (name "Net-(U$1-TXD0-GPIO43)") (class "Default")
      (node (ref "SV7") (pin "9") (pinfunction "9_9") (pintype "passive"))
      (node (ref "U$1") (pin "43") (pinfunction "TXD0-GPIO43_43") (pintype "bidirectional"))
    )
    (net (code "58") (name "Net-(U$1-USB_D+_GPIO20)") (class "Default")
      (node (ref "SV4") (pin "4") (pinfunction "4_4") (pintype "passive"))
      (node (ref "U$1") (pin "20") (pinfunction "USB_D+_GPIO20_20") (pintype "bidirectional"))
    )
    (net (code "59") (name "Net-(U$1-USB_D-_GPIO19)") (class "Default")
      (node (ref "SV4") (pin "3") (pinfunction "3_3") (pintype "passive"))
      (node (ref "U$1") (pin "19") (pinfunction "USB_D-_GPIO19_19") (pintype "bidirectional"))
    )
    (net (code "60") (name "Net-(U1-IO1)") (class "Default")
      (node (ref "U1") (pin "1") (pinfunction "IO1_1") (pintype "bidirectional"))
      (node (ref "UBS2") (pin "4") (pinfunction "S_4") (pintype "passive"))
      (node (ref "USB") (pin "1") (pinfunction "S_1") (pintype "passive"))
      (node (ref "USB-C") (pin "A7") (pinfunction "DN1_A7") (pintype "bidirectional"))
      (node (ref "USB-C") (pin "B7") (pinfunction "DN2_B7") (pintype "bidirectional"))
    )
    (net (code "61") (name "Net-(U1-IO2)") (class "Default")
      (node (ref "U1") (pin "3") (pinfunction "IO2_3") (pintype "bidirectional"))
      (node (ref "UBS2") (pin "5") (pinfunction "S_5") (pintype "passive"))
      (node (ref "USB") (pin "2") (pinfunction "S_2") (pintype "passive"))
      (node (ref "USB-C") (pin "A6") (pinfunction "DP1_A6") (pintype "bidirectional"))
      (node (ref "USB-C") (pin "B6") (pinfunction "DP2_B6") (pintype "bidirectional"))
    )
    (net (code "62") (name "Net-(U1-IO3)") (class "Default")
      (node (ref "R17") (pin "2") (pinfunction "2_2") (pintype "passive"))
      (node (ref "U1") (pin "4") (pinfunction "IO3_4") (pintype "bidirectional"))
      (node (ref "UBS2") (pin "2") (pinfunction "S_2") (pintype "passive"))
      (node (ref "USB-C") (pin "B5") (pinfunction "CC2_B5") (pintype "bidirectional"))
    )
    (net (code "63") (name "Net-(U1-IO4)") (class "Default")
      (node (ref "R18") (pin "2") (pinfunction "2_2") (pintype "passive"))
      (node (ref "U1") (pin "6") (pinfunction "IO4_6") (pintype "bidirectional"))
      (node (ref "UBS2") (pin "3") (pinfunction "S_3") (pintype "passive"))
      (node (ref "USB-C") (pin "A5") (pinfunction "CC1_A5") (pintype "bidirectional"))
    )
    (net (code "64") (name "unconnected-(M2-A3V3_5-Pad5)") (class "Default")
      (node (ref "M2") (pin "5") (pinfunction "A3V3_5_5") (pintype "bidirectional"))
    )
    (net (code "65") (name "unconnected-(M2-DEMP_2-Pad2)") (class "Default")
      (node (ref "M2") (pin "2") (pinfunction "DEMP_2_2") (pintype "bidirectional"))
    )
    (net (code "66") (name "unconnected-(M2-FLT_1-Pad1)") (class "Default")
      (node (ref "M2") (pin "1") (pinfunction "FLT_1_1") (pintype "bidirectional"))
    )
    (net (code "67") (name "unconnected-(M2-PadG1)") (class "Default")
      (node (ref "M2") (pin "G1") (pinfunction "G1_G1") (pintype "bidirectional"))
    )
    (net (code "68") (name "unconnected-(M2-XSMT_3-Pad3)") (class "Default")
      (node (ref "M2") (pin "3") (pinfunction "XSMT_3_3") (pintype "bidirectional"))
    )
    (net (code "69") (name "unconnected-(SD1-DAT1-Pad8)") (class "Default")
      (node (ref "SD1") (pin "8") (pinfunction "DAT1_8") (pintype "bidirectional"))
    )
    (net (code "70") (name "unconnected-(SD1-DAT2-Pad1)") (class "Default")
      (node (ref "SD1") (pin "1") (pinfunction "DAT2_1") (pintype "bidirectional"))
    )
    (net (code "71") (name "unconnected-(SD1-~{CARD}-Pad9)") (class "Default")
      (node (ref "SD1") (pin "9") (pinfunction "~{CARD}_9") (pintype "passive"))
    )
    (net (code "72") (name "unconnected-(USB-C-SBU1-PadA8)") (class "Default")
      (node (ref "USB-C") (pin "A8") (pinfunction "SBU1_A8") (pintype "bidirectional"))
    )
    (net (code "73") (name "unconnected-(USB-C-SBU2-PadB8)") (class "Default")
      (node (ref "USB-C") (pin "B8") (pinfunction "SBU2_B8") (pintype "bidirectional"))
    )
  )
)
